# Sheet7.net
KiCad netlist of a schematic drawn in Altium Designer
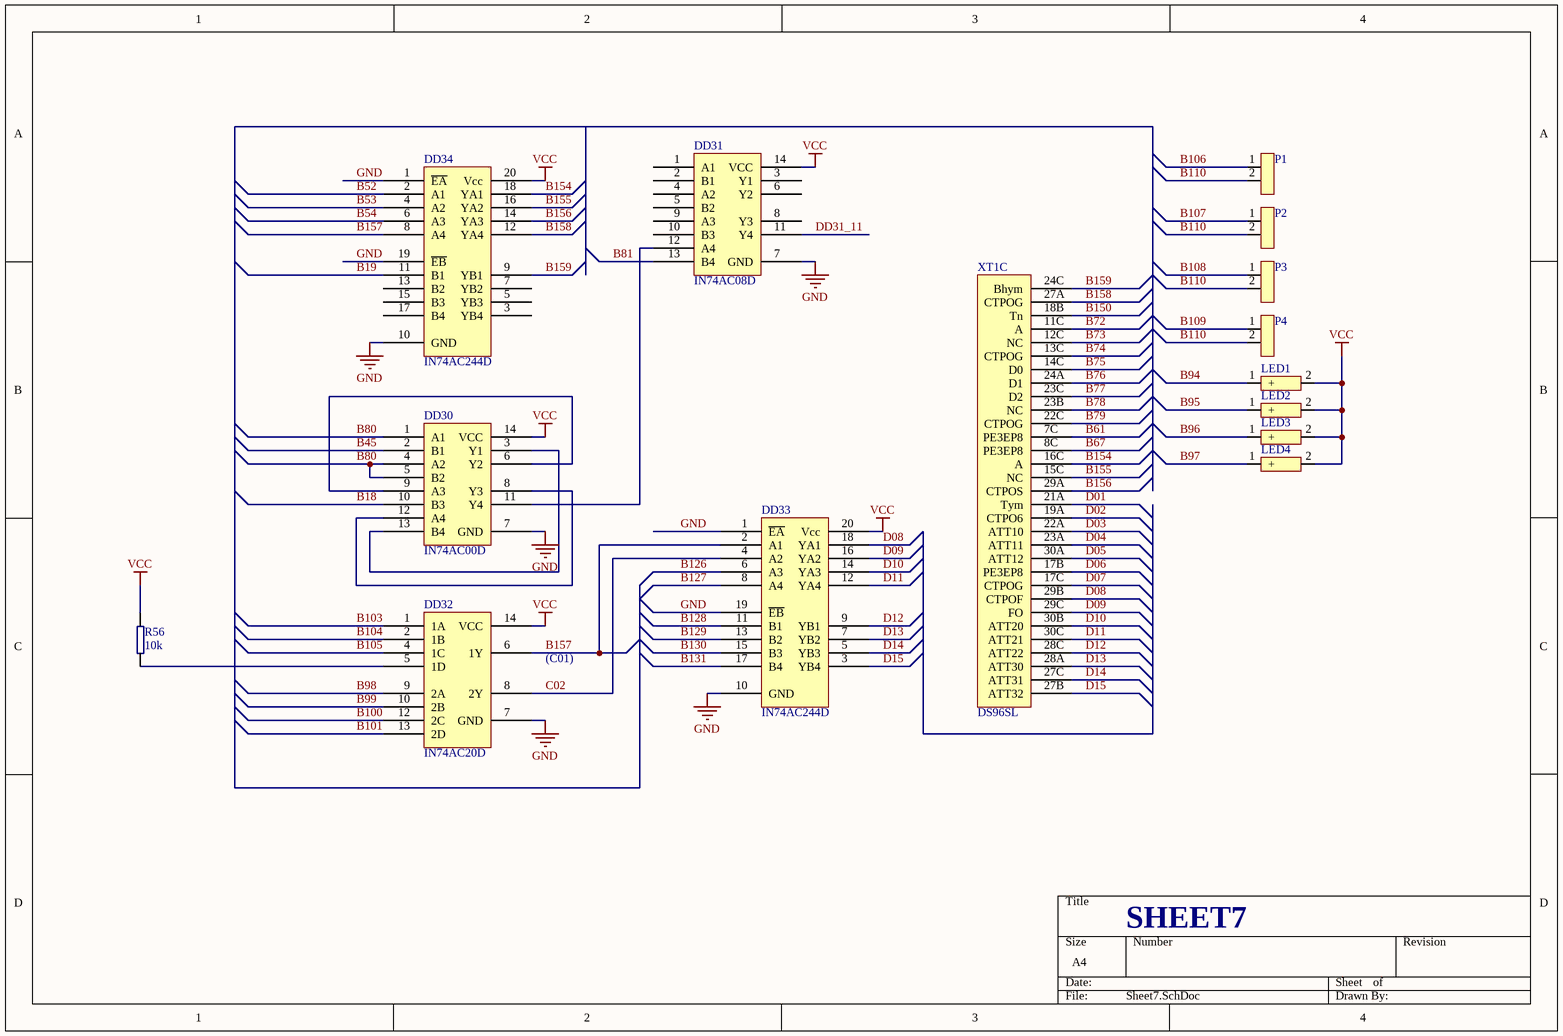
[diagram p0: Sheet7.SchDoc]

(export (version "E")
  (design (tool "Eeschema 10.0.6"))
  (components
    (comp (ref "DD30")
      (value "IN74AC00D")
      (footprint "14 SOIC-3.9")
      (libsource (lib "Board2") (part "IN74AC00D"))
    )
    (comp (ref "DD31")
      (value "IN74AC08D")
      (footprint "14 TSSOP-4.4")
      (libsource (lib "Board2") (part "IN74AC08D"))
    )
    (comp (ref "DD32")
      (value "IN74AC20D")
      (footprint "14 SOIC-3.9")
      (libsource (lib "Board2") (part "IN74AC20D"))
    )
    (comp (ref "DD33")
      (value "IN74AC244D")
      (footprint "20 SOIC-7.5")
      (libsource (lib "Board2") (part "IN74AC244D"))
    )
    (comp (ref "DD34")
      (value "IN74AC244D")
      (footprint "20 SOIC-7.5")
      (libsource (lib "*") (part "IN74AC244D"))
    )
    (comp (ref "LED1") (value "LED") (footprint "LED") (libsource (lib "Board2") (part "LED")))
    (comp (ref "LED2") (value "LED") (footprint "LED") (libsource (lib "Board2") (part "LED")))
    (comp (ref "LED3") (value "LED") (footprint "LED") (libsource (lib "Board2") (part "LED")))
    (comp (ref "LED4") (value "LED") (footprint "LED") (libsource (lib "Board2") (part "LED")))
    (comp (ref "P1") (value "PIN2") (footprint "2 SIP") (libsource (lib "Board2") (part "PIN2")))
    (comp (ref "P2") (value "PIN2") (footprint "2 SIP") (libsource (lib "Board2") (part "PIN2")))
    (comp (ref "P3") (value "PIN2") (footprint "2 SIP") (libsource (lib "Board2") (part "PIN2")))
    (comp (ref "P4") (value "PIN2") (footprint "2 SIP") (libsource (lib "Board2") (part "PIN2")))
    (comp (ref "R56")
      (value "10k")
      (footprint "0805")
      (fields (field (name "Comment") "R"))
      (libsource (lib "Board2") (part "R"))
    )
    (comp (ref "XT1") (value "DS96SL") (footprint "DS96") (libsource (lib "Board2") (part "DS96SL")))
  )
  (nets
    (net (code "1") (name "/B18") (class "Default")
      (node (ref "DD30") (pin "10") (pinfunction "B3_10") (pintype "passive"))
    )
    (net (code "2") (name "/B19") (class "Default")
      (node (ref "DD34") (pin "11") (pinfunction "B1_11") (pintype "passive"))
    )
    (net (code "3") (name "/B45") (class "Default")
      (node (ref "DD30") (pin "2") (pinfunction "B1_2") (pintype "passive"))
    )
    (net (code "4") (name "/B52") (class "Default")
      (node (ref "DD34") (pin "2") (pinfunction "A1_2") (pintype "passive"))
    )
    (net (code "5") (name "/B53") (class "Default")
      (node (ref "DD34") (pin "4") (pinfunction "A2_4") (pintype "passive"))
    )
    (net (code "6") (name "/B54") (class "Default")
      (node (ref "DD34") (pin "6") (pinfunction "A3_6") (pintype "passive"))
    )
    (net (code "7") (name "/B61") (class "Default")
      (node (ref "XT1") (pin "7C") (pinfunction "PE3EP8_7C") (pintype "passive"))
    )
    (net (code "8") (name "/B67") (class "Default")
      (node (ref "XT1") (pin "8C") (pinfunction "PE3EP8_8C") (pintype "passive"))
    )
    (net (code "9") (name "/B72") (class "Default")
      (node (ref "XT1") (pin "11C") (pinfunction "A_11C") (pintype "passive"))
    )
    (net (code "10") (name "/B73") (class "Default")
      (node (ref "XT1") (pin "12C") (pinfunction "NC_12C") (pintype "passive"))
    )
    (net (code "11") (name "/B74") (class "Default")
      (node (ref "XT1") (pin "13C") (pinfunction "CTPOG_13C") (pintype "passive"))
    )
    (net (code "12") (name "/B75") (class "Default")
      (node (ref "XT1") (pin "14C") (pinfunction "D0_14C") (pintype "passive"))
    )
    (net (code "13") (name "/B76") (class "Default")
      (node (ref "XT1") (pin "24A") (pinfunction "D1_24A") (pintype "passive"))
    )
    (net (code "14") (name "/B77") (class "Default")
      (node (ref "XT1") (pin "23C") (pinfunction "D2_23C") (pintype "passive"))
    )
    (net (code "15") (name "/B78") (class "Default")
      (node (ref "XT1") (pin "23B") (pinfunction "NC_23B") (pintype "passive"))
    )
    (net (code "16") (name "/B79") (class "Default")
      (node (ref "XT1") (pin "22C") (pinfunction "CTPOG_22C") (pintype "passive"))
    )
    (net (code "17") (name "/B80") (class "Default")
      (node (ref "DD30") (pin "1") (pinfunction "A1_1") (pintype "passive"))
      (node (ref "DD30") (pin "4") (pinfunction "A2_4") (pintype "passive"))
      (node (ref "DD30") (pin "5") (pinfunction "B2_5") (pintype "passive"))
    )
    (net (code "18") (name "/B81") (class "Default")
      (node (ref "DD31") (pin "13") (pinfunction "B4_13") (pintype "passive"))
    )
    (net (code "19") (name "/B94") (class "Default")
      (node (ref "LED1") (pin "1") (pinfunction "+_1") (pintype "passive"))
    )
    (net (code "20") (name "/B95") (class "Default")
      (node (ref "LED2") (pin "1") (pinfunction "+_1") (pintype "passive"))
    )
    (net (code "21") (name "/B96") (class "Default")
      (node (ref "LED3") (pin "1") (pinfunction "+_1") (pintype "passive"))
    )
    (net (code "22") (name "/B97") (class "Default")
      (node (ref "LED4") (pin "1") (pinfunction "+_1") (pintype "passive"))
    )
    (net (code "23") (name "/B98") (class "Default")
      (node (ref "DD32") (pin "9") (pinfunction "2A_9") (pintype "passive"))
    )
    (net (code "24") (name "/B99") (class "Default")
      (node (ref "DD32") (pin "10") (pinfunction "2B_10") (pintype "passive"))
    )
    (net (code "25") (name "/B100") (class "Default")
      (node (ref "DD32") (pin "12") (pinfunction "2C_12") (pintype "passive"))
    )
    (net (code "26") (name "/B101") (class "Default")
      (node (ref "DD32") (pin "13") (pinfunction "2D_13") (pintype "passive"))
    )
    (net (code "27") (name "/B103") (class "Default")
      (node (ref "DD32") (pin "1") (pinfunction "1A_1") (pintype "passive"))
    )
    (net (code "28") (name "/B104") (class "Default")
      (node (ref "DD32") (pin "2") (pinfunction "1B_2") (pintype "passive"))
    )
    (net (code "29") (name "/B105") (class "Default")
      (node (ref "DD32") (pin "4") (pinfunction "1C_4") (pintype "passive"))
    )
    (net (code "30") (name "/B106") (class "Default")
      (node (ref "P1") (pin "1") (pinfunction "1_1") (pintype "passive"))
    )
    (net (code "31") (name "/B107") (class "Default")
      (node (ref "P2") (pin "1") (pinfunction "1_1") (pintype "passive"))
    )
    (net (code "32") (name "/B108") (class "Default")
      (node (ref "P3") (pin "1") (pinfunction "1_1") (pintype "passive"))
    )
    (net (code "33") (name "/B109") (class "Default")
      (node (ref "P4") (pin "1") (pinfunction "1_1") (pintype "passive"))
    )
    (net (code "34") (name "/B110") (class "Default")
      (node (ref "P1") (pin "2") (pinfunction "2_2") (pintype "passive"))
      (node (ref "P2") (pin "2") (pinfunction "2_2") (pintype "passive"))
      (node (ref "P3") (pin "2") (pinfunction "2_2") (pintype "passive"))
      (node (ref "P4") (pin "2") (pinfunction "2_2") (pintype "passive"))
    )
    (net (code "35") (name "/B126") (class "Default")
      (node (ref "DD33") (pin "6") (pinfunction "A3_6") (pintype "passive"))
    )
    (net (code "36") (name "/B127") (class "Default")
      (node (ref "DD33") (pin "8") (pinfunction "A4_8") (pintype "passive"))
    )
    (net (code "37") (name "/B128") (class "Default")
      (node (ref "DD33") (pin "11") (pinfunction "B1_11") (pintype "passive"))
    )
    (net (code "38") (name "/B129") (class "Default")
      (node (ref "DD33") (pin "13") (pinfunction "B2_13") (pintype "passive"))
    )
    (net (code "39") (name "/B130") (class "Default")
      (node (ref "DD33") (pin "15") (pinfunction "B3_15") (pintype "passive"))
    )
    (net (code "40") (name "/B131") (class "Default")
      (node (ref "DD33") (pin "17") (pinfunction "B4_17") (pintype "passive"))
    )
    (net (code "41") (name "/B150") (class "Default")
      (node (ref "XT1") (pin "18B") (pinfunction "Tn_18B") (pintype "passive"))
    )
    (net (code "42") (name "/B154") (class "Default")
      (node (ref "DD34") (pin "18") (pinfunction "YA1_18") (pintype "passive"))
      (node (ref "XT1") (pin "16C") (pinfunction "A_16C") (pintype "passive"))
    )
    (net (code "43") (name "/B155") (class "Default")
      (node (ref "DD34") (pin "16") (pinfunction "YA2_16") (pintype "passive"))
      (node (ref "XT1") (pin "15C") (pinfunction "NC_15C") (pintype "passive"))
    )
    (net (code "44") (name "/B156") (class "Default")
      (node (ref "DD34") (pin "14") (pinfunction "YA3_14") (pintype "passive"))
      (node (ref "XT1") (pin "29A") (pinfunction "CTPOS_29A") (pintype "passive"))
    )
    (net (code "45") (name "/B157") (class "Default")
      (node (ref "DD32") (pin "6") (pinfunction "1Y_6") (pintype "passive"))
      (node (ref "DD33") (pin "2") (pinfunction "A1_2") (pintype "passive"))
      (node (ref "DD34") (pin "8") (pinfunction "A4_8") (pintype "passive"))
    )
    (net (code "46") (name "/B158") (class "Default")
      (node (ref "DD34") (pin "12") (pinfunction "YA4_12") (pintype "passive"))
      (node (ref "XT1") (pin "27A") (pinfunction "CTPOG_27A") (pintype "passive"))
    )
    (net (code "47") (name "/B159") (class "Default")
      (node (ref "DD34") (pin "9") (pinfunction "YB1_9") (pintype "passive"))
      (node (ref "XT1") (pin "24C") (pinfunction "Bhym_24C") (pintype "passive"))
    )
    (net (code "48") (name "/C02") (class "Default")
      (node (ref "DD32") (pin "8") (pinfunction "2Y_8") (pintype "passive"))
      (node (ref "DD33") (pin "4") (pinfunction "A2_4") (pintype "passive"))
    )
    (net (code "49") (name "/D01") (class "Default")
      (node (ref "XT1") (pin "21A") (pinfunction "Tym_21A") (pintype "passive"))
    )
    (net (code "50") (name "/D02") (class "Default")
      (node (ref "XT1") (pin "19A") (pinfunction "CTPO6_19A") (pintype "passive"))
    )
    (net (code "51") (name "/D03") (class "Default")
      (node (ref "XT1") (pin "22A") (pinfunction "ATT10_22A") (pintype "passive"))
    )
    (net (code "52") (name "/D04") (class "Default")
      (node (ref "XT1") (pin "23A") (pinfunction "ATT11_23A") (pintype "passive"))
    )
    (net (code "53") (name "/D05") (class "Default")
      (node (ref "XT1") (pin "30A") (pinfunction "ATT12_30A") (pintype "passive"))
    )
    (net (code "54") (name "/D06") (class "Default")
      (node (ref "XT1") (pin "17B") (pinfunction "PE3EP8_17B") (pintype "passive"))
    )
    (net (code "55") (name "/D07") (class "Default")
      (node (ref "XT1") (pin "17C") (pinfunction "CTPOG_17C") (pintype "passive"))
    )
    (net (code "56") (name "/D08") (class "Default")
      (node (ref "DD33") (pin "18") (pinfunction "YA1_18") (pintype "passive"))
      (node (ref "XT1") (pin "29B") (pinfunction "CTPOF_29B") (pintype "passive"))
    )
    (net (code "57") (name "/D09") (class "Default")
      (node (ref "DD33") (pin "16") (pinfunction "YA2_16") (pintype "passive"))
      (node (ref "XT1") (pin "29C") (pinfunction "FO_29C") (pintype "passive"))
    )
    (net (code "58") (name "/D10") (class "Default")
      (node (ref "DD33") (pin "14") (pinfunction "YA3_14") (pintype "passive"))
      (node (ref "XT1") (pin "30B") (pinfunction "ATT20_30B") (pintype "passive"))
    )
    (net (code "59") (name "/D11") (class "Default")
      (node (ref "DD33") (pin "12") (pinfunction "YA4_12") (pintype "passive"))
      (node (ref "XT1") (pin "30C") (pinfunction "ATT21_30C") (pintype "passive"))
    )
    (net (code "60") (name "/D12") (class "Default")
      (node (ref "DD33") (pin "9") (pinfunction "YB1_9") (pintype "passive"))
      (node (ref "XT1") (pin "28C") (pinfunction "ATT22_28C") (pintype "passive"))
    )
    (net (code "61") (name "/D13") (class "Default")
      (node (ref "DD33") (pin "7") (pinfunction "YB2_7") (pintype "passive"))
      (node (ref "XT1") (pin "28A") (pinfunction "ATT30_28A") (pintype "passive"))
    )
    (net (code "62") (name "/D14") (class "Default")
      (node (ref "DD33") (pin "5") (pinfunction "YB3_5") (pintype "passive"))
      (node (ref "XT1") (pin "27C") (pinfunction "ATT31_27C") (pintype "passive"))
    )
    (net (code "63") (name "/D15") (class "Default")
      (node (ref "DD33") (pin "3") (pinfunction "YB4_3") (pintype "passive"))
      (node (ref "XT1") (pin "27B") (pinfunction "ATT32_27B") (pintype "passive"))
    )
    (net (code "64") (name "/DD31_11") (class "Default")
      (node (ref "DD31") (pin "11") (pinfunction "Y4_11") (pintype "passive"))
    )
    (net (code "65") (name "GND") (class "Default")
      (node (ref "DD30") (pin "7") (pinfunction "GND_7") (pintype "passive"))
      (node (ref "DD31") (pin "7") (pinfunction "GND_7") (pintype "passive"))
      (node (ref "DD32") (pin "7") (pinfunction "GND_7") (pintype "passive"))
      (node (ref "DD33") (pin "1") (pinfunction "~{EA}_1") (pintype "passive"))
      (node (ref "DD33") (pin "10") (pinfunction "GND_10") (pintype "passive"))
      (node (ref "DD33") (pin "19") (pinfunction "~{EB}_19") (pintype "passive"))
      (node (ref "DD34") (pin "1") (pinfunction "~{EA}_1") (pintype "passive"))
      (node (ref "DD34") (pin "10") (pinfunction "GND_10") (pintype "passive"))
      (node (ref "DD34") (pin "19") (pinfunction "~{EB}_19") (pintype "passive"))
    )
    (net (code "66") (name "Net-(DD30-A3)") (class "Default")
      (node (ref "DD30") (pin "6") (pinfunction "Y2_6") (pintype "passive"))
      (node (ref "DD30") (pin "9") (pinfunction "A3_9") (pintype "passive"))
    )
    (net (code "67") (name "Net-(DD30-A4)") (class "Default")
      (node (ref "DD30") (pin "12") (pinfunction "A4_12") (pintype "passive"))
      (node (ref "DD30") (pin "8") (pinfunction "Y3_8") (pintype "passive"))
    )
    (net (code "68") (name "Net-(DD30-B4)") (class "Default")
      (node (ref "DD30") (pin "13") (pinfunction "B4_13") (pintype "passive"))
      (node (ref "DD30") (pin "3") (pinfunction "Y1_3") (pintype "passive"))
    )
    (net (code "69") (name "Net-(DD30-Y4)") (class "Default")
      (node (ref "DD30") (pin "11") (pinfunction "Y4_11") (pintype "passive"))
      (node (ref "DD31") (pin "12") (pinfunction "A4_12") (pintype "passive"))
    )
    (net (code "70") (name "Net-(DD32-1D)") (class "Default")
      (node (ref "DD32") (pin "5") (pinfunction "1D_5") (pintype "passive"))
      (node (ref "R56") (pin "2") (pinfunction "0_2") (pintype "passive"))
    )
    (net (code "71") (name "VCC") (class "Default")
      (node (ref "DD30") (pin "14") (pinfunction "VCC_14") (pintype "passive"))
      (node (ref "DD31") (pin "14") (pinfunction "VCC_14") (pintype "passive"))
      (node (ref "DD32") (pin "14") (pinfunction "VCC_14") (pintype "passive"))
      (node (ref "DD33") (pin "20") (pinfunction "Vcc_20") (pintype "passive"))
      (node (ref "DD34") (pin "20") (pinfunction "Vcc_20") (pintype "passive"))
      (node (ref "LED1") (pin "2") (pintype "passive"))
      (node (ref "LED2") (pin "2") (pintype "passive"))
      (node (ref "LED3") (pin "2") (pintype "passive"))
      (node (ref "LED4") (pin "2") (pintype "passive"))
      (node (ref "R56") (pin "1") (pinfunction "1_1") (pintype "passive"))
    )
    (net (code "72") (name "unconnected-(DD31-A1-Pad1)") (class "Default")
      (node (ref "DD31") (pin "1") (pinfunction "A1_1") (pintype "passive"))
    )
    (net (code "73") (name "unconnected-(DD31-A2-Pad4)") (class "Default")
      (node (ref "DD31") (pin "4") (pinfunction "A2_4") (pintype "passive"))
    )
    (net (code "74") (name "unconnected-(DD31-A3-Pad9)") (class "Default")
      (node (ref "DD31") (pin "9") (pinfunction "A3_9") (pintype "passive"))
    )
    (net (code "75") (name "unconnected-(DD31-B1-Pad2)") (class "Default")
      (node (ref "DD31") (pin "2") (pinfunction "B1_2") (pintype "passive"))
    )
    (net (code "76") (name "unconnected-(DD31-B2-Pad5)") (class "Default")
      (node (ref "DD31") (pin "5") (pinfunction "B2_5") (pintype "passive"))
    )
    (net (code "77") (name "unconnected-(DD31-B3-Pad10)") (class "Default")
      (node (ref "DD31") (pin "10") (pinfunction "B3_10") (pintype "passive"))
    )
    (net (code "78") (name "unconnected-(DD31-Y1-Pad3)") (class "Default")
      (node (ref "DD31") (pin "3") (pinfunction "Y1_3") (pintype "passive"))
    )
    (net (code "79") (name "unconnected-(DD31-Y2-Pad6)") (class "Default")
      (node (ref "DD31") (pin "6") (pinfunction "Y2_6") (pintype "passive"))
    )
    (net (code "80") (name "unconnected-(DD31-Y3-Pad8)") (class "Default")
      (node (ref "DD31") (pin "8") (pinfunction "Y3_8") (pintype "passive"))
    )
    (net (code "81") (name "unconnected-(DD34-B2-Pad13)") (class "Default")
      (node (ref "DD34") (pin "13") (pinfunction "B2_13") (pintype "passive"))
    )
    (net (code "82") (name "unconnected-(DD34-B3-Pad15)") (class "Default")
      (node (ref "DD34") (pin "15") (pinfunction "B3_15") (pintype "passive"))
    )
    (net (code "83") (name "unconnected-(DD34-B4-Pad17)") (class "Default")
      (node (ref "DD34") (pin "17") (pinfunction "B4_17") (pintype "passive"))
    )
    (net (code "84") (name "unconnected-(DD34-YB2-Pad7)") (class "Default")
      (node (ref "DD34") (pin "7") (pinfunction "YB2_7") (pintype "passive"))
    )
    (net (code "85") (name "unconnected-(DD34-YB3-Pad5)") (class "Default")
      (node (ref "DD34") (pin "5") (pinfunction "YB3_5") (pintype "passive"))
    )
    (net (code "86") (name "unconnected-(DD34-YB4-Pad3)") (class "Default")
      (node (ref "DD34") (pin "3") (pinfunction "YB4_3") (pintype "passive"))
    )
  )
)
